# UTAP2022_DAUGHTER_v1_0.net
KiCad netlist of a schematic drawn in EAGLE
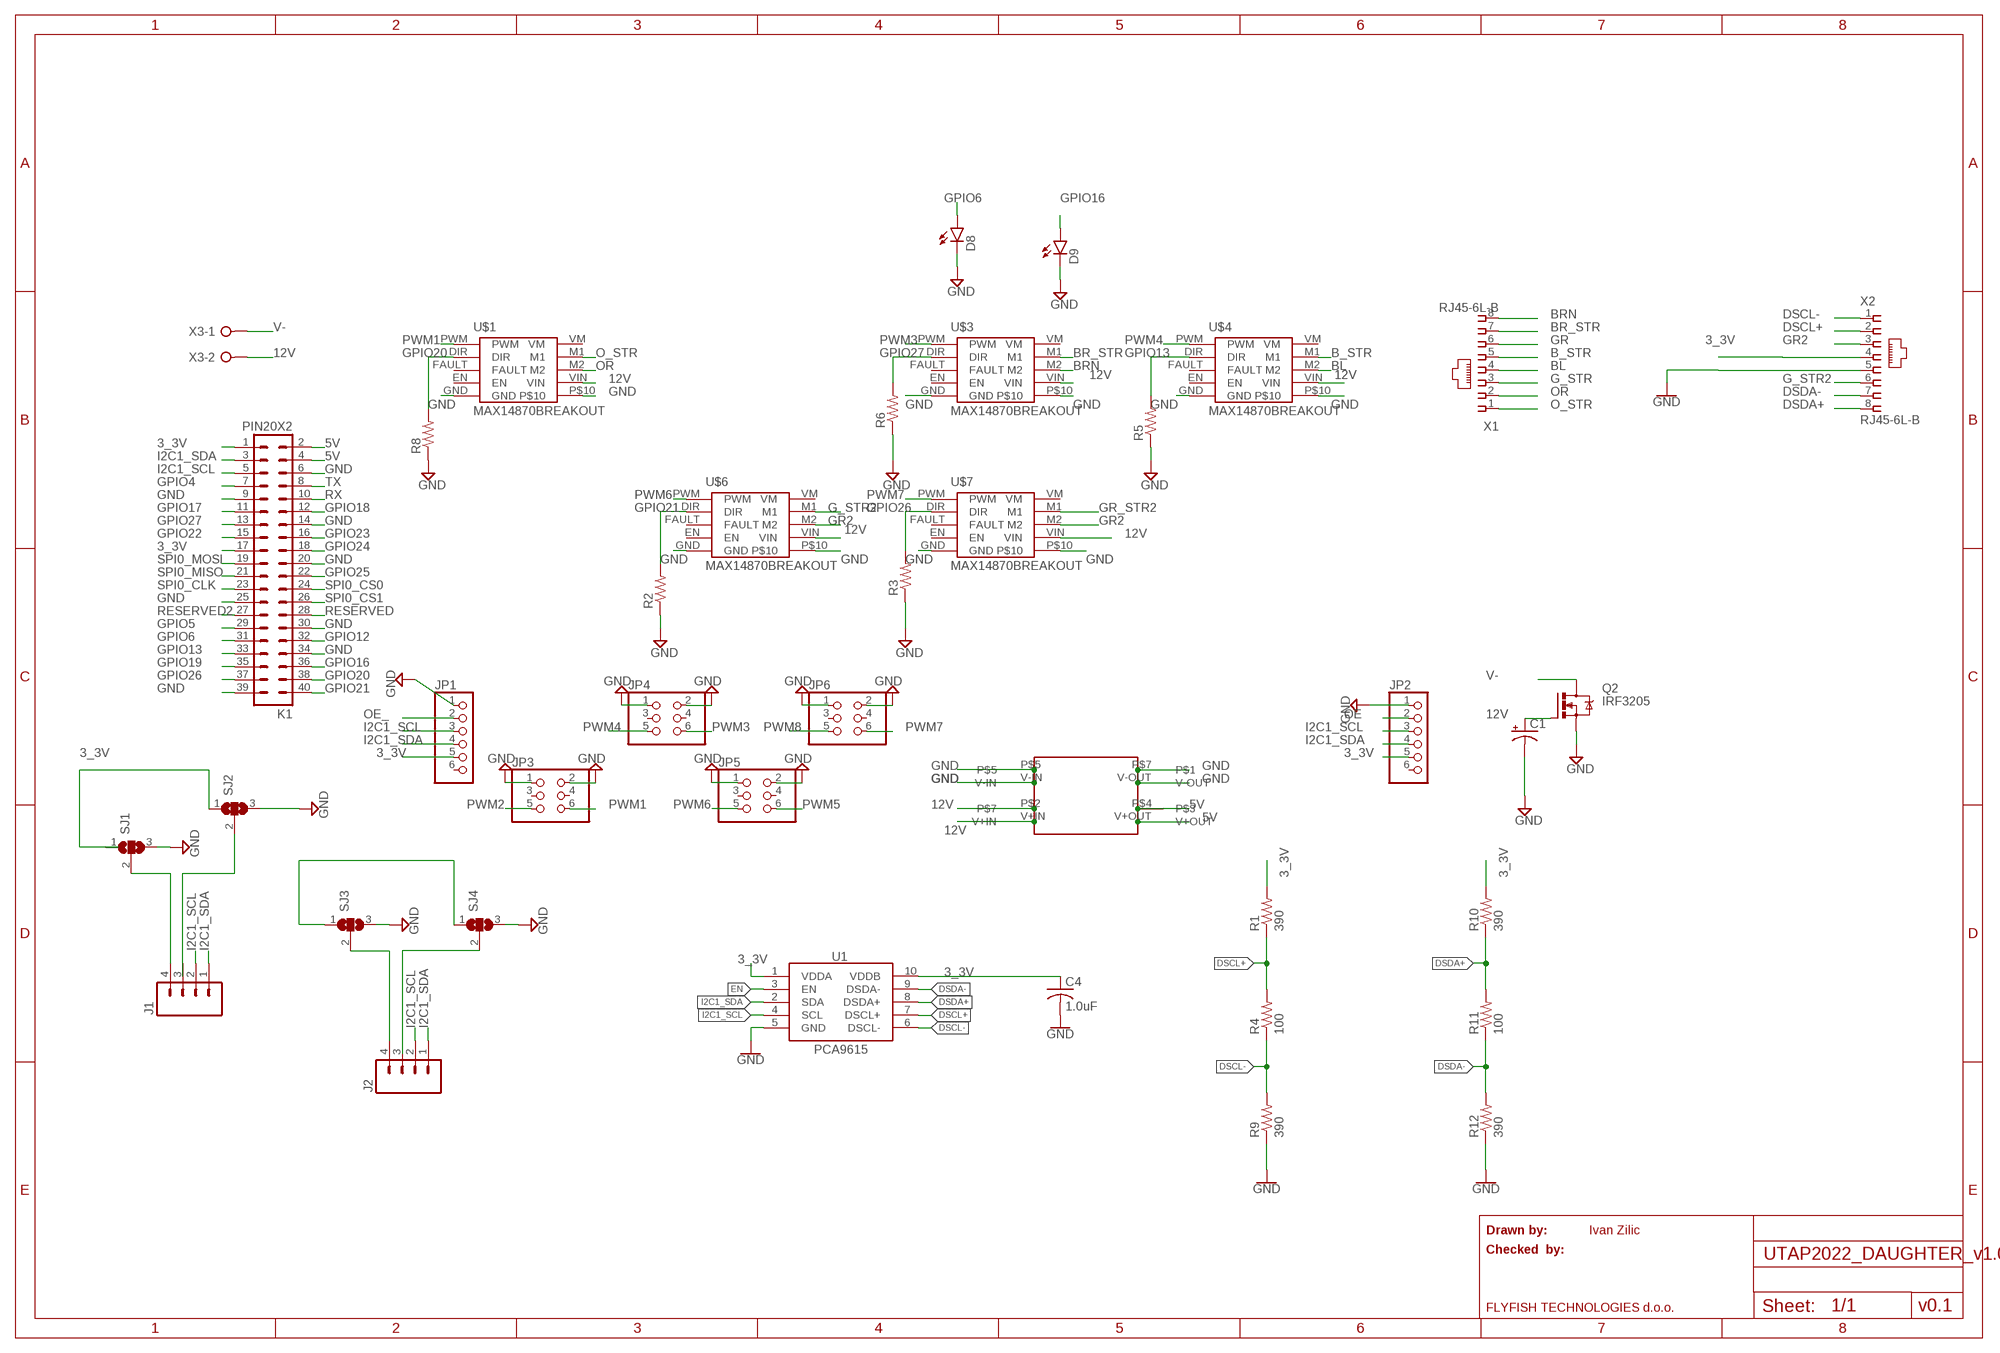
[diagram p0: schematic, sheet 1]

(export (version "E")
  (design (tool "Eeschema 10.0.6"))
  (components
    (comp (ref "C1")
      (value "CAP_POLPTH1")
      (footprint "eagle-import:CPOL-RADIAL-100UF-25V")
      (libsource (lib "eagle-import") (part "CAP_POLPTH1"))
    )
    (comp (ref "C4")
      (value "1.0uF")
      (footprint "eagle-import:C050-024X044")
      (libsource (lib "eagle-import") (part "C-US050-024X044"))
    )
    (comp (ref "D8")
      (value "LED5MM")
      (footprint "eagle-import:LED5MM")
      (libsource (lib "eagle-import") (part "LED5MM"))
    )
    (comp (ref "D9")
      (value "LED5MM")
      (footprint "eagle-import:LED5MM")
      (libsource (lib "eagle-import") (part "LED5MM"))
    )
    (comp (ref "J1")
      (value "M04PTH")
      (footprint "eagle-import:1X04")
      (libsource (lib "eagle-import") (part "M04PTH"))
    )
    (comp (ref "J2")
      (value "M04PTH")
      (footprint "eagle-import:1X04")
      (libsource (lib "eagle-import") (part "M04PTH"))
    )
    (comp (ref "JP1")
      (value "PINHD-1X6")
      (footprint "eagle-import:1X06")
      (libsource (lib "eagle-import") (part "PINHD-1X6"))
    )
    (comp (ref "JP2")
      (value "PINHD-1X6")
      (footprint "eagle-import:1X06")
      (libsource (lib "eagle-import") (part "PINHD-1X6"))
    )
    (comp (ref "JP3")
      (value "PINHD-2X3")
      (footprint "eagle-import:2X03")
      (libsource (lib "eagle-import") (part "PINHD-2X3"))
    )
    (comp (ref "JP4")
      (value "PINHD-2X3")
      (footprint "eagle-import:2X03")
      (libsource (lib "eagle-import") (part "PINHD-2X3"))
    )
    (comp (ref "JP5")
      (value "PINHD-2X3")
      (footprint "eagle-import:2X03")
      (libsource (lib "eagle-import") (part "PINHD-2X3"))
    )
    (comp (ref "JP6")
      (value "PINHD-2X3")
      (footprint "eagle-import:2X03")
      (libsource (lib "eagle-import") (part "PINHD-2X3"))
    )
    (comp (ref "K1")
      (value "PIN20X2")
      (footprint "eagle-import:PIN_20X2")
      (libsource (lib "eagle-import") (part "PIN20X2"))
    )
    (comp (ref "Q2")
      (value "IRF3205")
      (footprint "eagle-import:TO220BV")
      (libsource (lib "eagle-import") (part "IRF540"))
    )
    (comp (ref "R1")
      (value "390")
      (footprint "eagle-import:0204_7")
      (libsource (lib "eagle-import") (part "R-US_0204/7"))
    )
    (comp (ref "R2")
      (value "R-US_0204/7")
      (footprint "eagle-import:0204_7")
      (libsource (lib "eagle-import") (part "R-US_0204/7"))
    )
    (comp (ref "R3")
      (value "R-US_0204/7")
      (footprint "eagle-import:0204_7")
      (libsource (lib "eagle-import") (part "R-US_0204/7"))
    )
    (comp (ref "R4")
      (value "100")
      (footprint "eagle-import:0204_7")
      (libsource (lib "eagle-import") (part "R-US_0204/7"))
    )
    (comp (ref "R5")
      (value "R-US_0204/7")
      (footprint "eagle-import:0204_7")
      (libsource (lib "eagle-import") (part "R-US_0204/7"))
    )
    (comp (ref "R6")
      (value "R-US_0204/7")
      (footprint "eagle-import:0204_7")
      (libsource (lib "eagle-import") (part "R-US_0204/7"))
    )
    (comp (ref "R8")
      (value "R-US_0204/7")
      (footprint "eagle-import:0204_7")
      (libsource (lib "eagle-import") (part "R-US_0204/7"))
    )
    (comp (ref "R9")
      (value "390")
      (footprint "eagle-import:0204_7")
      (libsource (lib "eagle-import") (part "R-US_0204/7"))
    )
    (comp (ref "R10")
      (value "390")
      (footprint "eagle-import:0204_7")
      (libsource (lib "eagle-import") (part "R-US_0204/7"))
    )
    (comp (ref "R11")
      (value "100")
      (footprint "eagle-import:0204_7")
      (libsource (lib "eagle-import") (part "R-US_0204/7"))
    )
    (comp (ref "R12")
      (value "390")
      (footprint "eagle-import:0204_7")
      (libsource (lib "eagle-import") (part "R-US_0204/7"))
    )
    (comp (ref "SJ1")
      (value "SJ2W")
      (footprint "eagle-import:SJ_2")
      (libsource (lib "eagle-import") (part "SJ2W"))
    )
    (comp (ref "SJ2")
      (value "SJ2W")
      (footprint "eagle-import:SJ_2")
      (libsource (lib "eagle-import") (part "SJ2W"))
    )
    (comp (ref "SJ3")
      (value "SJ2W")
      (footprint "eagle-import:SJ_2")
      (libsource (lib "eagle-import") (part "SJ2W"))
    )
    (comp (ref "SJ4")
      (value "SJ2W")
      (footprint "eagle-import:SJ_2")
      (libsource (lib "eagle-import") (part "SJ2W"))
    )
    (comp (ref "U$1")
      (value "MAX14870BREAKOUT")
      (footprint "eagle-import:MAX14870_BREAKOUT")
      (libsource (lib "eagle-import") (part "MAX14870BREAKOUT"))
    )
    (comp (ref "U$3")
      (value "MAX14870BREAKOUT")
      (footprint "eagle-import:MAX14870_BREAKOUT")
      (libsource (lib "eagle-import") (part "MAX14870BREAKOUT"))
    )
    (comp (ref "U$4")
      (value "MAX14870BREAKOUT")
      (footprint "eagle-import:MAX14870_BREAKOUT")
      (libsource (lib "eagle-import") (part "MAX14870BREAKOUT"))
    )
    (comp (ref "U$6")
      (value "MAX14870BREAKOUT")
      (footprint "eagle-import:MAX14870_BREAKOUT")
      (libsource (lib "eagle-import") (part "MAX14870BREAKOUT"))
    )
    (comp (ref "U$7")
      (value "MAX14870BREAKOUT")
      (footprint "eagle-import:MAX14870_BREAKOUT")
      (libsource (lib "eagle-import") (part "MAX14870BREAKOUT"))
    )
    (comp (ref "U$9")
      (value "MP1584EN")
      (footprint "eagle-import:BUCK_CONV")
      (libsource (lib "eagle-import") (part "MP1584EN"))
    )
    (comp (ref "U1")
      (value "PCA9615")
      (footprint "eagle-import:TSSOP10")
      (libsource (lib "eagle-import") (part "PCA9615"))
    )
    (comp (ref "X1")
      (value "RJ45-6L-B")
      (footprint "eagle-import:RJ45-NO-SHIELD")
      (libsource (lib "eagle-import") (part "RJ45-6L-B"))
    )
    (comp (ref "X2")
      (value "RJ45-6L-B")
      (footprint "eagle-import:RJ45-NO-SHIELD")
      (libsource (lib "eagle-import") (part "RJ45-6L-B"))
    )
    (comp (ref "X3")
      (value "W237-02P")
      (footprint "eagle-import:W237-132")
      (libsource (lib "eagle-import") (part "W237-02P"))
    )
  )
  (nets
    (net (code "1") (name "/3_3V") (class "Default")
      (node (ref "C4") (pin "1") (pinfunction "1_1") (pintype "passive"))
      (node (ref "JP1") (pin "5") (pinfunction "5_5") (pintype "passive"))
      (node (ref "JP2") (pin "5") (pinfunction "5_5") (pintype "passive"))
      (node (ref "K1") (pin "1") (pinfunction "1_1") (pintype "passive"))
      (node (ref "K1") (pin "17") (pinfunction "17_17") (pintype "passive"))
      (node (ref "R1") (pin "2") (pinfunction "2_2") (pintype "passive"))
      (node (ref "R10") (pin "2") (pinfunction "2_2") (pintype "passive"))
      (node (ref "SJ2") (pin "1") (pinfunction "1_1") (pintype "passive"))
      (node (ref "SJ3") (pin "1") (pinfunction "1_1") (pintype "passive"))
      (node (ref "SJ4") (pin "1") (pinfunction "1_1") (pintype "passive"))
      (node (ref "U1") (pin "1") (pinfunction "VDDA_1") (pintype "bidirectional"))
      (node (ref "U1") (pin "10") (pinfunction "VDDB_10") (pintype "bidirectional"))
      (node (ref "X2") (pin "4") (pinfunction "4_4") (pintype "passive"))
    )
    (net (code "2") (name "/5V") (class "Default")
      (node (ref "K1") (pin "2") (pinfunction "2_2") (pintype "passive"))
      (node (ref "K1") (pin "4") (pinfunction "4_4") (pintype "passive"))
      (node (ref "U$9") (pin "P$4") (pinfunction "P$3_P$4") (pintype "bidirectional"))
      (node (ref "U$9") (pin "V+OUT") (pinfunction "V+OUT_V+OUT") (pintype "bidirectional"))
    )
    (net (code "3") (name "/12V") (class "Default")
      (node (ref "C1") (pin "1") (pinfunction "+_1") (pintype "passive"))
      (node (ref "Q2") (pin "G") (pinfunction "G_G") (pintype "passive"))
      (node (ref "U$1") (pin "VIN") (pinfunction "VIN_VIN") (pintype "bidirectional"))
      (node (ref "U$3") (pin "VIN") (pinfunction "VIN_VIN") (pintype "bidirectional"))
      (node (ref "U$4") (pin "VIN") (pinfunction "VIN_VIN") (pintype "bidirectional"))
      (node (ref "U$6") (pin "VIN") (pinfunction "VIN_VIN") (pintype "bidirectional"))
      (node (ref "U$7") (pin "VIN") (pinfunction "VIN_VIN") (pintype "bidirectional"))
      (node (ref "U$9") (pin "P$2") (pinfunction "P$7_P$2") (pintype "bidirectional"))
      (node (ref "U$9") (pin "V+IN") (pinfunction "V+IN_V+IN") (pintype "bidirectional"))
      (node (ref "X3") (pin "2") (pinfunction "KL_2") (pintype "passive"))
    )
    (net (code "4") (name "/BL") (class "Default")
      (node (ref "U$4") (pin "M2") (pinfunction "M2_M2") (pintype "bidirectional"))
      (node (ref "X1") (pin "4") (pinfunction "4_4") (pintype "passive"))
    )
    (net (code "5") (name "/BRN") (class "Default")
      (node (ref "U$3") (pin "M2") (pinfunction "M2_M2") (pintype "bidirectional"))
      (node (ref "X1") (pin "8") (pinfunction "8_8") (pintype "passive"))
    )
    (net (code "6") (name "/BR_STR") (class "Default")
      (node (ref "U$3") (pin "M1") (pinfunction "M1_M1") (pintype "bidirectional"))
      (node (ref "X1") (pin "7") (pinfunction "7_7") (pintype "passive"))
    )
    (net (code "7") (name "/B_STR") (class "Default")
      (node (ref "U$4") (pin "M1") (pinfunction "M1_M1") (pintype "bidirectional"))
      (node (ref "X1") (pin "5") (pinfunction "5_5") (pintype "passive"))
    )
    (net (code "8") (name "/GPIO4") (class "Default")
      (node (ref "K1") (pin "7") (pinfunction "7_7") (pintype "passive"))
    )
    (net (code "9") (name "/GPIO5") (class "Default")
      (node (ref "K1") (pin "29") (pinfunction "29_29") (pintype "passive"))
    )
    (net (code "10") (name "/GPIO6") (class "Default")
      (node (ref "D8") (pin "A") (pinfunction "A_A") (pintype "passive"))
      (node (ref "K1") (pin "31") (pinfunction "31_31") (pintype "passive"))
    )
    (net (code "11") (name "/GPIO12") (class "Default")
      (node (ref "K1") (pin "32") (pinfunction "32_32") (pintype "passive"))
    )
    (net (code "12") (name "/GPIO13") (class "Default")
      (node (ref "K1") (pin "33") (pinfunction "33_33") (pintype "passive"))
      (node (ref "R5") (pin "2") (pinfunction "2_2") (pintype "passive"))
      (node (ref "U$4") (pin "DIR") (pinfunction "DIR_DIR") (pintype "bidirectional"))
    )
    (net (code "13") (name "/GPIO16") (class "Default")
      (node (ref "D9") (pin "A") (pinfunction "A_A") (pintype "passive"))
      (node (ref "K1") (pin "36") (pinfunction "36_36") (pintype "passive"))
    )
    (net (code "14") (name "/GPIO17") (class "Default")
      (node (ref "K1") (pin "11") (pinfunction "11_11") (pintype "passive"))
    )
    (net (code "15") (name "/GPIO18") (class "Default")
      (node (ref "K1") (pin "12") (pinfunction "12_12") (pintype "passive"))
    )
    (net (code "16") (name "/GPIO19") (class "Default")
      (node (ref "K1") (pin "35") (pinfunction "35_35") (pintype "passive"))
    )
    (net (code "17") (name "/GPIO20") (class "Default")
      (node (ref "K1") (pin "38") (pinfunction "38_38") (pintype "passive"))
      (node (ref "R8") (pin "2") (pinfunction "2_2") (pintype "passive"))
      (node (ref "U$1") (pin "DIR") (pinfunction "DIR_DIR") (pintype "bidirectional"))
    )
    (net (code "18") (name "/GPIO21") (class "Default")
      (node (ref "K1") (pin "40") (pinfunction "40_40") (pintype "passive"))
      (node (ref "R2") (pin "2") (pinfunction "2_2") (pintype "passive"))
      (node (ref "U$6") (pin "DIR") (pinfunction "DIR_DIR") (pintype "bidirectional"))
    )
    (net (code "19") (name "/GPIO22") (class "Default")
      (node (ref "K1") (pin "15") (pinfunction "15_15") (pintype "passive"))
    )
    (net (code "20") (name "/GPIO23") (class "Default")
      (node (ref "K1") (pin "16") (pinfunction "16_16") (pintype "passive"))
    )
    (net (code "21") (name "/GPIO24") (class "Default")
      (node (ref "K1") (pin "18") (pinfunction "18_18") (pintype "passive"))
    )
    (net (code "22") (name "/GPIO25") (class "Default")
      (node (ref "K1") (pin "22") (pinfunction "22_22") (pintype "passive"))
    )
    (net (code "23") (name "/GPIO26") (class "Default")
      (node (ref "K1") (pin "37") (pinfunction "37_37") (pintype "passive"))
      (node (ref "R3") (pin "2") (pinfunction "2_2") (pintype "passive"))
      (node (ref "U$7") (pin "DIR") (pinfunction "DIR_DIR") (pintype "bidirectional"))
    )
    (net (code "24") (name "/GPIO27") (class "Default")
      (node (ref "K1") (pin "13") (pinfunction "13_13") (pintype "passive"))
      (node (ref "R6") (pin "2") (pinfunction "2_2") (pintype "passive"))
      (node (ref "U$3") (pin "DIR") (pinfunction "DIR_DIR") (pintype "bidirectional"))
    )
    (net (code "25") (name "/GR") (class "Default")
      (node (ref "X1") (pin "6") (pinfunction "6_6") (pintype "passive"))
    )
    (net (code "26") (name "/GR2") (class "Default")
      (node (ref "U$6") (pin "M2") (pinfunction "M2_M2") (pintype "bidirectional"))
      (node (ref "U$7") (pin "M2") (pinfunction "M2_M2") (pintype "bidirectional"))
      (node (ref "X2") (pin "3") (pinfunction "3_3") (pintype "passive"))
    )
    (net (code "27") (name "/GR_STR2") (class "Default")
      (node (ref "U$7") (pin "M1") (pinfunction "M1_M1") (pintype "bidirectional"))
    )
    (net (code "28") (name "/G_STR") (class "Default")
      (node (ref "X1") (pin "3") (pinfunction "3_3") (pintype "passive"))
    )
    (net (code "29") (name "/G_STR2") (class "Default")
      (node (ref "U$6") (pin "M1") (pinfunction "M1_M1") (pintype "bidirectional"))
      (node (ref "X2") (pin "6") (pinfunction "6_6") (pintype "passive"))
    )
    (net (code "30") (name "/OE") (class "Default")
      (node (ref "JP2") (pin "2") (pinfunction "2_2") (pintype "passive"))
    )
    (net (code "31") (name "/OE_") (class "Default")
      (node (ref "JP1") (pin "2") (pinfunction "2_2") (pintype "passive"))
    )
    (net (code "32") (name "/OR") (class "Default")
      (node (ref "U$1") (pin "M2") (pinfunction "M2_M2") (pintype "bidirectional"))
      (node (ref "X1") (pin "2") (pinfunction "2_2") (pintype "passive"))
    )
    (net (code "33") (name "/O_STR") (class "Default")
      (node (ref "U$1") (pin "M1") (pinfunction "M1_M1") (pintype "bidirectional"))
      (node (ref "X1") (pin "1") (pinfunction "1_1") (pintype "passive"))
    )
    (net (code "34") (name "/PWM1") (class "Default")
      (node (ref "JP3") (pin "6") (pinfunction "6_6") (pintype "passive"))
      (node (ref "U$1") (pin "PWM") (pinfunction "PWM_PWM") (pintype "bidirectional"))
    )
    (net (code "35") (name "/PWM2") (class "Default")
      (node (ref "JP3") (pin "5") (pinfunction "5_5") (pintype "passive"))
    )
    (net (code "36") (name "/PWM3") (class "Default")
      (node (ref "JP4") (pin "6") (pinfunction "6_6") (pintype "passive"))
      (node (ref "U$3") (pin "PWM") (pinfunction "PWM_PWM") (pintype "bidirectional"))
    )
    (net (code "37") (name "/PWM4") (class "Default")
      (node (ref "JP4") (pin "5") (pinfunction "5_5") (pintype "passive"))
      (node (ref "U$4") (pin "PWM") (pinfunction "PWM_PWM") (pintype "bidirectional"))
    )
    (net (code "38") (name "/PWM5") (class "Default")
      (node (ref "JP5") (pin "6") (pinfunction "6_6") (pintype "passive"))
    )
    (net (code "39") (name "/PWM6") (class "Default")
      (node (ref "JP5") (pin "5") (pinfunction "5_5") (pintype "passive"))
      (node (ref "U$6") (pin "PWM") (pinfunction "PWM_PWM") (pintype "bidirectional"))
    )
    (net (code "40") (name "/PWM7") (class "Default")
      (node (ref "JP6") (pin "6") (pinfunction "6_6") (pintype "passive"))
      (node (ref "U$7") (pin "PWM") (pinfunction "PWM_PWM") (pintype "bidirectional"))
    )
    (net (code "41") (name "/PWM8") (class "Default")
      (node (ref "JP6") (pin "5") (pinfunction "5_5") (pintype "passive"))
    )
    (net (code "42") (name "/RESERVED") (class "Default")
      (node (ref "K1") (pin "28") (pinfunction "28_28") (pintype "passive"))
    )
    (net (code "43") (name "/RESERVED2") (class "Default")
      (node (ref "K1") (pin "27") (pinfunction "27_27") (pintype "passive"))
    )
    (net (code "44") (name "/RX") (class "Default")
      (node (ref "K1") (pin "10") (pinfunction "10_10") (pintype "passive"))
    )
    (net (code "45") (name "/SPI0_CLK") (class "Default")
      (node (ref "K1") (pin "23") (pinfunction "23_23") (pintype "passive"))
    )
    (net (code "46") (name "/SPI0_CS0") (class "Default")
      (node (ref "K1") (pin "24") (pinfunction "24_24") (pintype "passive"))
    )
    (net (code "47") (name "/SPI0_CS1") (class "Default")
      (node (ref "K1") (pin "26") (pinfunction "26_26") (pintype "passive"))
    )
    (net (code "48") (name "/SPI0_MISO") (class "Default")
      (node (ref "K1") (pin "21") (pinfunction "21_21") (pintype "passive"))
    )
    (net (code "49") (name "/SPI0_MOSI") (class "Default")
      (node (ref "K1") (pin "19") (pinfunction "19_19") (pintype "passive"))
    )
    (net (code "50") (name "/TX") (class "Default")
      (node (ref "K1") (pin "8") (pinfunction "8_8") (pintype "passive"))
    )
    (net (code "51") (name "/V-") (class "Default")
      (node (ref "Q2") (pin "D") (pinfunction "D_D") (pintype "passive"))
      (node (ref "X3") (pin "1") (pinfunction "KL_1") (pintype "passive"))
    )
    (net (code "52") (name "DSCL+") (class "Default")
      (node (ref "R1") (pin "1") (pinfunction "1_1") (pintype "passive"))
      (node (ref "R4") (pin "2") (pinfunction "2_2") (pintype "passive"))
      (node (ref "U1") (pin "7") (pinfunction "DSCL+_7") (pintype "bidirectional"))
      (node (ref "X2") (pin "2") (pinfunction "2_2") (pintype "passive"))
    )
    (net (code "53") (name "DSCL-") (class "Default")
      (node (ref "R4") (pin "1") (pinfunction "1_1") (pintype "passive"))
      (node (ref "R9") (pin "2") (pinfunction "2_2") (pintype "passive"))
      (node (ref "U1") (pin "6") (pinfunction "DSCL-_6") (pintype "bidirectional"))
      (node (ref "X2") (pin "1") (pinfunction "1_1") (pintype "passive"))
    )
    (net (code "54") (name "DSDA+") (class "Default")
      (node (ref "R10") (pin "1") (pinfunction "1_1") (pintype "passive"))
      (node (ref "R11") (pin "2") (pinfunction "2_2") (pintype "passive"))
      (node (ref "U1") (pin "8") (pinfunction "DSDA+_8") (pintype "bidirectional"))
      (node (ref "X2") (pin "8") (pinfunction "8_8") (pintype "passive"))
    )
    (net (code "55") (name "DSDA-") (class "Default")
      (node (ref "R11") (pin "1") (pinfunction "1_1") (pintype "passive"))
      (node (ref "R12") (pin "2") (pinfunction "2_2") (pintype "passive"))
      (node (ref "U1") (pin "9") (pinfunction "DSDA-_9") (pintype "bidirectional"))
      (node (ref "X2") (pin "7") (pinfunction "7_7") (pintype "passive"))
    )
    (net (code "56") (name "EN") (class "Default")
      (node (ref "U1") (pin "3") (pinfunction "EN_3") (pintype "bidirectional"))
    )
    (net (code "57") (name "GND") (class "Default")
      (node (ref "C1") (pin "2") (pinfunction "-_2") (pintype "passive"))
      (node (ref "C4") (pin "2") (pinfunction "2_2") (pintype "passive"))
      (node (ref "D8") (pin "K") (pinfunction "C_K") (pintype "passive"))
      (node (ref "D9") (pin "K") (pinfunction "C_K") (pintype "passive"))
      (node (ref "JP1") (pin "1") (pinfunction "1_1") (pintype "passive"))
      (node (ref "JP2") (pin "1") (pinfunction "1_1") (pintype "passive"))
      (node (ref "JP3") (pin "1") (pinfunction "1_1") (pintype "passive"))
      (node (ref "JP3") (pin "2") (pinfunction "2_2") (pintype "passive"))
      (node (ref "JP4") (pin "1") (pinfunction "1_1") (pintype "passive"))
      (node (ref "JP4") (pin "2") (pinfunction "2_2") (pintype "passive"))
      (node (ref "JP5") (pin "1") (pinfunction "1_1") (pintype "passive"))
      (node (ref "JP5") (pin "2") (pinfunction "2_2") (pintype "passive"))
      (node (ref "JP6") (pin "1") (pinfunction "1_1") (pintype "passive"))
      (node (ref "JP6") (pin "2") (pinfunction "2_2") (pintype "passive"))
      (node (ref "K1") (pin "14") (pinfunction "14_14") (pintype "passive"))
      (node (ref "K1") (pin "20") (pinfunction "20_20") (pintype "passive"))
      (node (ref "K1") (pin "25") (pinfunction "25_25") (pintype "passive"))
      (node (ref "K1") (pin "30") (pinfunction "30_30") (pintype "passive"))
      (node (ref "K1") (pin "34") (pinfunction "34_34") (pintype "passive"))
      (node (ref "K1") (pin "39") (pinfunction "39_39") (pintype "passive"))
      (node (ref "K1") (pin "6") (pinfunction "6_6") (pintype "passive"))
      (node (ref "K1") (pin "9") (pinfunction "9_9") (pintype "passive"))
      (node (ref "Q2") (pin "S") (pinfunction "S_S") (pintype "passive"))
      (node (ref "R12") (pin "1") (pinfunction "1_1") (pintype "passive"))
      (node (ref "R2") (pin "1") (pinfunction "1_1") (pintype "passive"))
      (node (ref "R3") (pin "1") (pinfunction "1_1") (pintype "passive"))
      (node (ref "R5") (pin "1") (pinfunction "1_1") (pintype "passive"))
      (node (ref "R6") (pin "1") (pinfunction "1_1") (pintype "passive"))
      (node (ref "R8") (pin "1") (pinfunction "1_1") (pintype "passive"))
      (node (ref "R9") (pin "1") (pinfunction "1_1") (pintype "passive"))
      (node (ref "SJ1") (pin "3") (pinfunction "3_3") (pintype "passive"))
      (node (ref "SJ2") (pin "3") (pinfunction "3_3") (pintype "passive"))
      (node (ref "SJ3") (pin "3") (pinfunction "3_3") (pintype "passive"))
      (node (ref "SJ4") (pin "3") (pinfunction "3_3") (pintype "passive"))
      (node (ref "U$1") (pin "GND") (pinfunction "GND_GND") (pintype "bidirectional"))
      (node (ref "U$1") (pin "P$10") (pinfunction "P$10_P$10") (pintype "bidirectional"))
      (node (ref "U$3") (pin "GND") (pinfunction "GND_GND") (pintype "bidirectional"))
      (node (ref "U$3") (pin "P$10") (pinfunction "P$10_P$10") (pintype "bidirectional"))
      (node (ref "U$4") (pin "GND") (pinfunction "GND_GND") (pintype "bidirectional"))
      (node (ref "U$4") (pin "P$10") (pinfunction "P$10_P$10") (pintype "bidirectional"))
      (node (ref "U$6") (pin "GND") (pinfunction "GND_GND") (pintype "bidirectional"))
      (node (ref "U$6") (pin "P$10") (pinfunction "P$10_P$10") (pintype "bidirectional"))
      (node (ref "U$7") (pin "GND") (pinfunction "GND_GND") (pintype "bidirectional"))
      (node (ref "U$7") (pin "P$10") (pinfunction "P$10_P$10") (pintype "bidirectional"))
      (node (ref "U$9") (pin "P$5") (pinfunction "P$5_P$5") (pintype "bidirectional"))
      (node (ref "U$9") (pin "P$7") (pinfunction "P$1_P$7") (pintype "bidirectional"))
      (node (ref "U$9") (pin "V-IN") (pinfunction "V-IN_V-IN") (pintype "bidirectional"))
      (node (ref "U$9") (pin "V-OUT") (pinfunction "V-OUT_V-OUT") (pintype "bidirectional"))
      (node (ref "U1") (pin "5") (pinfunction "GND_5") (pintype "bidirectional"))
      (node (ref "X2") (pin "5") (pinfunction "5_5") (pintype "passive"))
    )
    (net (code "58") (name "I2C1_SCL") (class "Default")
      (node (ref "J1") (pin "2") (pinfunction "2_2") (pintype "passive"))
      (node (ref "J2") (pin "2") (pinfunction "2_2") (pintype "passive"))
      (node (ref "JP1") (pin "3") (pinfunction "3_3") (pintype "passive"))
      (node (ref "JP2") (pin "3") (pinfunction "3_3") (pintype "passive"))
      (node (ref "K1") (pin "5") (pinfunction "5_5") (pintype "passive"))
      (node (ref "U1") (pin "4") (pinfunction "SCL_4") (pintype "bidirectional"))
    )
    (net (code "59") (name "I2C1_SDA") (class "Default")
      (node (ref "J1") (pin "1") (pinfunction "1_1") (pintype "passive"))
      (node (ref "J2") (pin "1") (pinfunction "1_1") (pintype "passive"))
      (node (ref "JP1") (pin "4") (pinfunction "4_4") (pintype "passive"))
      (node (ref "JP2") (pin "4") (pinfunction "4_4") (pintype "passive"))
      (node (ref "K1") (pin "3") (pinfunction "3_3") (pintype "passive"))
      (node (ref "U1") (pin "2") (pinfunction "SDA_2") (pintype "bidirectional"))
    )
    (net (code "60") (name "Net-(J1-Pad4)") (class "Default")
      (node (ref "J1") (pin "4") (pinfunction "4_4") (pintype "passive"))
      (node (ref "SJ1") (pin "2") (pinfunction "2_2") (pintype "passive"))
    )
    (net (code "61") (name "Net-(J2-Pad4)") (class "Default")
      (node (ref "J2") (pin "4") (pinfunction "4_4") (pintype "passive"))
      (node (ref "SJ3") (pin "2") (pinfunction "2_2") (pintype "passive"))
    )
    (net (code "62") (name "unconnected-(J1-Pad3)") (class "Default")
      (node (ref "J1") (pin "3") (pinfunction "3_3") (pintype "passive"))
    )
    (net (code "63") (name "unconnected-(J2-Pad3)") (class "Default")
      (node (ref "J2") (pin "3") (pinfunction "3_3") (pintype "passive"))
    )
    (net (code "64") (name "unconnected-(JP1-Pad6)") (class "Default")
      (node (ref "JP1") (pin "6") (pinfunction "6_6") (pintype "passive"))
    )
    (net (code "65") (name "unconnected-(JP2-Pad6)") (class "Default")
      (node (ref "JP2") (pin "6") (pinfunction "6_6") (pintype "passive"))
    )
    (net (code "66") (name "unconnected-(JP3-Pad3)") (class "Default")
      (node (ref "JP3") (pin "3") (pinfunction "3_3") (pintype "passive"))
    )
    (net (code "67") (name "unconnected-(JP3-Pad4)") (class "Default")
      (node (ref "JP3") (pin "4") (pinfunction "4_4") (pintype "passive"))
    )
    (net (code "68") (name "unconnected-(JP4-Pad3)") (class "Default")
      (node (ref "JP4") (pin "3") (pinfunction "3_3") (pintype "passive"))
    )
    (net (code "69") (name "unconnected-(JP4-Pad4)") (class "Default")
      (node (ref "JP4") (pin "4") (pinfunction "4_4") (pintype "passive"))
    )
    (net (code "70") (name "unconnected-(JP5-Pad3)") (class "Default")
      (node (ref "JP5") (pin "3") (pinfunction "3_3") (pintype "passive"))
    )
    (net (code "71") (name "unconnected-(JP5-Pad4)") (class "Default")
      (node (ref "JP5") (pin "4") (pinfunction "4_4") (pintype "passive"))
    )
    (net (code "72") (name "unconnected-(JP6-Pad3)") (class "Default")
      (node (ref "JP6") (pin "3") (pinfunction "3_3") (pintype "passive"))
    )
    (net (code "73") (name "unconnected-(JP6-Pad4)") (class "Default")
      (node (ref "JP6") (pin "4") (pinfunction "4_4") (pintype "passive"))
    )
    (net (code "74") (name "unconnected-(SJ1-Pad1)") (class "Default")
      (node (ref "SJ1") (pin "1") (pinfunction "1_1") (pintype "passive"))
    )
    (net (code "75") (name "unconnected-(SJ2-Pad2)") (class "Default")
      (node (ref "SJ2") (pin "2") (pinfunction "2_2") (pintype "passive"))
    )
    (net (code "76") (name "unconnected-(SJ4-Pad2)") (class "Default")
      (node (ref "SJ4") (pin "2") (pinfunction "2_2") (pintype "passive"))
    )
    (net (code "77") (name "unconnected-(U$1-PadEN)") (class "Default")
      (node (ref "U$1") (pin "EN") (pinfunction "EN_EN") (pintype "bidirectional"))
    )
    (net (code "78") (name "unconnected-(U$1-PadFAULT)") (class "Default")
      (node (ref "U$1") (pin "FAULT") (pinfunction "FAULT_FAULT") (pintype "bidirectional"))
    )
    (net (code "79") (name "unconnected-(U$1-PadVM)") (class "Default")
      (node (ref "U$1") (pin "VM") (pinfunction "VM_VM") (pintype "bidirectional"))
    )
    (net (code "80") (name "unconnected-(U$3-PadEN)") (class "Default")
      (node (ref "U$3") (pin "EN") (pinfunction "EN_EN") (pintype "bidirectional"))
    )
    (net (code "81") (name "unconnected-(U$3-PadFAULT)") (class "Default")
      (node (ref "U$3") (pin "FAULT") (pinfunction "FAULT_FAULT") (pintype "bidirectional"))
    )
    (net (code "82") (name "unconnected-(U$3-PadVM)") (class "Default")
      (node (ref "U$3") (pin "VM") (pinfunction "VM_VM") (pintype "bidirectional"))
    )
    (net (code "83") (name "unconnected-(U$4-PadEN)") (class "Default")
      (node (ref "U$4") (pin "EN") (pinfunction "EN_EN") (pintype "bidirectional"))
    )
    (net (code "84") (name "unconnected-(U$4-PadFAULT)") (class "Default")
      (node (ref "U$4") (pin "FAULT") (pinfunction "FAULT_FAULT") (pintype "bidirectional"))
    )
    (net (code "85") (name "unconnected-(U$4-PadVM)") (class "Default")
      (node (ref "U$4") (pin "VM") (pinfunction "VM_VM") (pintype "bidirectional"))
    )
    (net (code "86") (name "unconnected-(U$6-PadEN)") (class "Default")
      (node (ref "U$6") (pin "EN") (pinfunction "EN_EN") (pintype "bidirectional"))
    )
    (net (code "87") (name "unconnected-(U$6-PadFAULT)") (class "Default")
      (node (ref "U$6") (pin "FAULT") (pinfunction "FAULT_FAULT") (pintype "bidirectional"))
    )
    (net (code "88") (name "unconnected-(U$6-PadVM)") (class "Default")
      (node (ref "U$6") (pin "VM") (pinfunction "VM_VM") (pintype "bidirectional"))
    )
    (net (code "89") (name "unconnected-(U$7-PadEN)") (class "Default")
      (node (ref "U$7") (pin "EN") (pinfunction "EN_EN") (pintype "bidirectional"))
    )
    (net (code "90") (name "unconnected-(U$7-PadFAULT)") (class "Default")
      (node (ref "U$7") (pin "FAULT") (pinfunction "FAULT_FAULT") (pintype "bidirectional"))
    )
    (net (code "91") (name "unconnected-(U$7-PadVM)") (class "Default")
      (node (ref "U$7") (pin "VM") (pinfunction "VM_VM") (pintype "bidirectional"))
    )
  )
)
